# MCU.net
KiCad netlist of a schematic drawn in Altium Designer
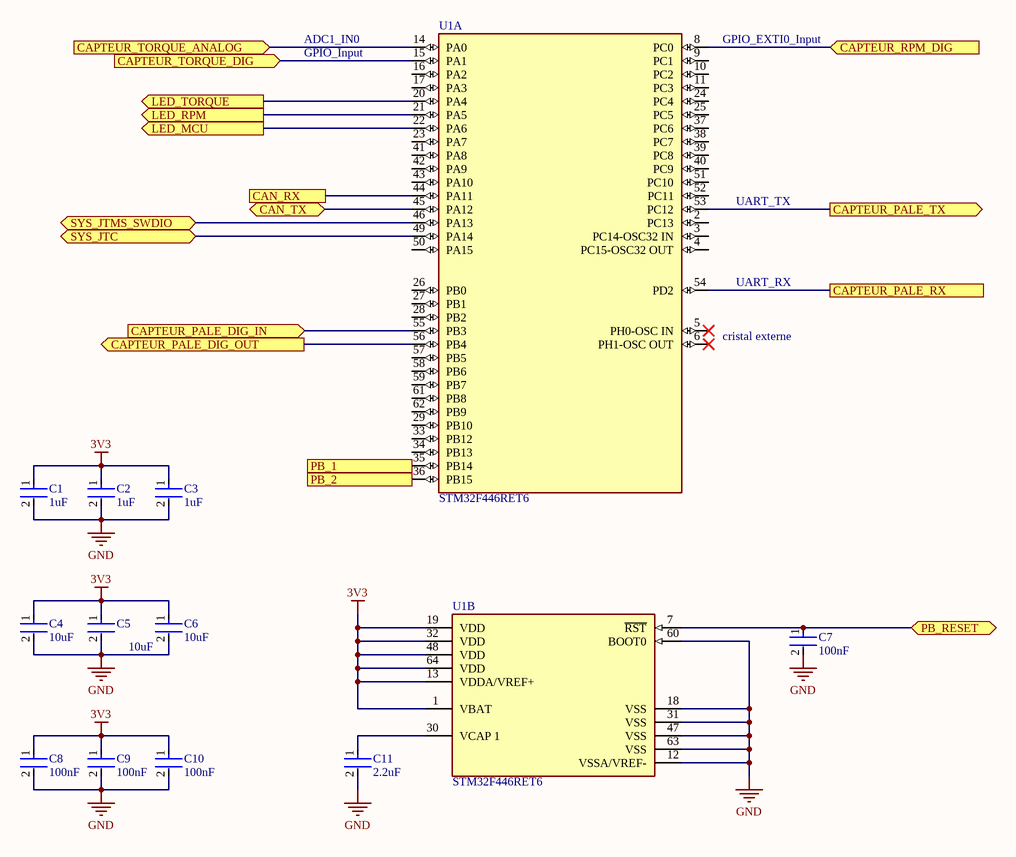
[diagram p0: MCU.SchDoc]

(export (version "E")
  (design (tool "Eeschema 10.0.6"))
  (components
    (comp (ref "C1")
      (value "1uF")
      (footprint "FP-GRM155-0_05-IPC_A")
      (description "Multilayer Ceramic Capacitor, 1 uF, 25 V, ± 20%, X5R, 0402 [1005 Metric]")
      (fields
        (field (name "MANUFACTURER") "Murata")
        (field (name "MANUFACTURER PART NUMBER") "GRM155R61E105MA12D")
      )
      (libsource (lib "chinook_lib_symbol_rotor") (part "GRM155R61E105MA12D"))
    )
    (comp (ref "C2")
      (value "1uF")
      (footprint "FP-GRM155-0_05-IPC_A")
      (description "Multilayer Ceramic Capacitor, 1 uF, 25 V, ± 20%, X5R, 0402 [1005 Metric]")
      (fields
        (field (name "MANUFACTURER") "Murata")
        (field (name "MANUFACTURER PART NUMBER") "GRM155R61E105MA12D")
      )
      (libsource (lib "chinook_lib_symbol_rotor") (part "GRM155R61E105MA12D"))
    )
    (comp (ref "C3")
      (value "1uF")
      (footprint "FP-GRM155-0_05-IPC_A")
      (description "Multilayer Ceramic Capacitor, 1 uF, 25 V, ± 20%, X5R, 0402 [1005 Metric]")
      (fields
        (field (name "MANUFACTURER") "Murata")
        (field (name "MANUFACTURER PART NUMBER") "GRM155R61E105MA12D")
      )
      (libsource (lib "chinook_lib_symbol_rotor") (part "GRM155R61E105MA12D"))
    )
    (comp (ref "C4")
      (value "10uF")
      (footprint "FP-GRM155-0_15-MFG")
      (description "Multilayer Ceramic Capacitor, 10 uF, 6.3 V, ± 20%, X5R, 0402 [1005 Metric]")
      (fields
        (field (name "MANUFACTURER") "Murata")
        (field (name "MANUFACTURER PART NUMBER") "GRM155R60J106ME15D")
      )
      (libsource (lib "chinook_lib_symbol_rotor") (part "GRM155R60J106ME15D"))
    )
    (comp (ref "C5")
      (value "10uF")
      (footprint "FP-GRM155-0_15-MFG")
      (description "Multilayer Ceramic Capacitor, 10 uF, 6.3 V, ± 20%, X5R, 0402 [1005 Metric]")
      (fields
        (field (name "MANUFACTURER") "Murata")
        (field (name "MANUFACTURER PART NUMBER") "GRM155R60J106ME15D")
      )
      (libsource (lib "chinook_lib_symbol_rotor") (part "GRM155R60J106ME15D"))
    )
    (comp (ref "C6")
      (value "10uF")
      (footprint "FP-GRM155-0_15-MFG")
      (description "Multilayer Ceramic Capacitor, 10 uF, 6.3 V, ± 20%, X5R, 0402 [1005 Metric]")
      (fields
        (field (name "MANUFACTURER") "Murata")
        (field (name "MANUFACTURER PART NUMBER") "GRM155R60J106ME15D")
      )
      (libsource (lib "chinook_lib_symbol_rotor") (part "GRM155R60J106ME15D"))
    )
    (comp (ref "C7")
      (value "100nF")
      (footprint "FP-CL278-IPC_A")
      (description "Multilayer Ceramic Capacitor, 0.1 uF, 25 V, ± 10%, X5R, 0402 [1005 Metric]")
      (fields
        (field (name "MANUFACTURER") "Samsung")
        (field (name "MANUFACTURER PART NUMBER") "CL05A104KA5NNNC")
      )
      (libsource (lib "chinook_lib_symbol_rotor") (part "CL05A104KA5NNNC"))
    )
    (comp (ref "C8")
      (value "100nF")
      (footprint "FP-CL278-IPC_A")
      (description "Multilayer Ceramic Capacitor, 0.1 uF, 25 V, ± 10%, X5R, 0402 [1005 Metric]")
      (fields
        (field (name "MANUFACTURER") "Samsung")
        (field (name "MANUFACTURER PART NUMBER") "CL05A104KA5NNNC")
      )
      (libsource (lib "chinook_lib_symbol_rotor") (part "CL05A104KA5NNNC"))
    )
    (comp (ref "C9")
      (value "100nF")
      (footprint "FP-CL278-IPC_A")
      (description "Multilayer Ceramic Capacitor, 0.1 uF, 25 V, ± 10%, X5R, 0402 [1005 Metric]")
      (fields
        (field (name "MANUFACTURER") "Samsung")
        (field (name "MANUFACTURER PART NUMBER") "CL05A104KA5NNNC")
      )
      (libsource (lib "chinook_lib_symbol_rotor") (part "CL05A104KA5NNNC"))
    )
    (comp (ref "C10")
      (value "100nF")
      (footprint "FP-CL278-IPC_A")
      (description "Multilayer Ceramic Capacitor, 0.1 uF, 25 V, ± 10%, X5R, 0402 [1005 Metric]")
      (fields
        (field (name "MANUFACTURER") "Samsung")
        (field (name "MANUFACTURER PART NUMBER") "CL05A104KA5NNNC")
      )
      (libsource (lib "chinook_lib_symbol_rotor") (part "CL05A104KA5NNNC"))
    )
    (comp (ref "C11")
      (value "2.2uF")
      (footprint "FP-GRM155-0_05-MFG")
      (description "Cap Ceramic 2.2uF 6.3V X6S 10% Pad SMD 0402 105°C T/R")
      (fields
        (field (name "MANUFACTURER") "Murata")
        (field (name "MANUFACTURER PART NUMBER") "GRM155C80J225KE95D")
      )
      (libsource (lib "chinook_lib_symbol_rotor") (part "GRM155C80J225KE95D"))
    )
    (comp (ref "U1")
      (value "STM32F446RET6")
      (footprint "FP-LQFP64-5W-IPC_A")
      (description "MCU 32-bit ARM Cortex M4 RISC 512KB Flash 2.5V/3.3V Medical 64-Pin LQFP Frame")
      (fields (field (name "MANUFACTURER") "STMicroelectronics"))
      (libsource (lib "chinook_lib_symbol_rotor") (part "STM32F446RET6"))
    )
  )
  (nets
    (net (code "1") (name "/CAN_RX") (class "Default")
      (node (ref "U1") (pin "44") (pinfunction "PA11_44") (pintype "bidirectional"))
    )
    (net (code "2") (name "/CAN_TX") (class "Default")
      (node (ref "U1") (pin "45") (pinfunction "PA12_45") (pintype "bidirectional"))
    )
    (net (code "3") (name "/CAPTEUR_PALE_DIG_IN") (class "Default")
      (node (ref "U1") (pin "55") (pinfunction "PB3_55") (pintype "bidirectional"))
    )
    (net (code "4") (name "/CAPTEUR_PALE_DIG_OUT") (class "Default")
      (node (ref "U1") (pin "56") (pinfunction "PB4_56") (pintype "bidirectional"))
    )
    (net (code "5") (name "/CAPTEUR_PALE_RX") (class "Default")
      (node (ref "U1") (pin "54") (pinfunction "PD2_54") (pintype "bidirectional"))
    )
    (net (code "6") (name "/CAPTEUR_PALE_TX") (class "Default")
      (node (ref "U1") (pin "53") (pinfunction "PC12_53") (pintype "bidirectional"))
    )
    (net (code "7") (name "/CAPTEUR_RPM_DIG") (class "Default")
      (node (ref "U1") (pin "8") (pinfunction "PC0_8") (pintype "bidirectional"))
    )
    (net (code "8") (name "/CAPTEUR_TORQUE_ANALOG") (class "Default")
      (node (ref "U1") (pin "14") (pinfunction "PA0_14") (pintype "bidirectional"))
    )
    (net (code "9") (name "/CAPTEUR_TORQUE_DIG") (class "Default")
      (node (ref "U1") (pin "15") (pinfunction "PA1_15") (pintype "bidirectional"))
    )
    (net (code "10") (name "/LED_MCU") (class "Default")
      (node (ref "U1") (pin "22") (pinfunction "PA6_22") (pintype "bidirectional"))
    )
    (net (code "11") (name "/LED_RPM") (class "Default")
      (node (ref "U1") (pin "21") (pinfunction "PA5_21") (pintype "bidirectional"))
    )
    (net (code "12") (name "/LED_TORQUE") (class "Default")
      (node (ref "U1") (pin "20") (pinfunction "PA4_20") (pintype "bidirectional"))
    )
    (net (code "13") (name "/PB_1") (class "Default")
      (node (ref "U1") (pin "35") (pinfunction "PB14_35") (pintype "bidirectional"))
    )
    (net (code "14") (name "/PB_2") (class "Default")
      (node (ref "U1") (pin "36") (pinfunction "PB15_36") (pintype "bidirectional"))
    )
    (net (code "15") (name "/PB_RESET") (class "Default")
      (node (ref "C7") (pin "1") (pinfunction "1_1") (pintype "passive"))
      (node (ref "U1") (pin "7") (pinfunction "~{RST}_7") (pintype "input"))
    )
    (net (code "16") (name "/SYS_JTC") (class "Default")
      (node (ref "U1") (pin "49") (pinfunction "PA14_49") (pintype "bidirectional"))
    )
    (net (code "17") (name "/SYS_JTMS_SWDIO") (class "Default")
      (node (ref "U1") (pin "46") (pinfunction "PA13_46") (pintype "bidirectional"))
    )
    (net (code "18") (name "3V3") (class "Default")
      (node (ref "C1") (pin "1") (pinfunction "1_1") (pintype "passive"))
      (node (ref "C10") (pin "1") (pinfunction "1_1") (pintype "passive"))
      (node (ref "C2") (pin "1") (pinfunction "1_1") (pintype "passive"))
      (node (ref "C3") (pin "1") (pinfunction "1_1") (pintype "passive"))
      (node (ref "C4") (pin "1") (pinfunction "1_1") (pintype "passive"))
      (node (ref "C5") (pin "1") (pinfunction "1_1") (pintype "passive"))
      (node (ref "C6") (pin "1") (pinfunction "1_1") (pintype "passive"))
      (node (ref "C8") (pin "1") (pinfunction "1_1") (pintype "passive"))
      (node (ref "C9") (pin "1") (pinfunction "1_1") (pintype "passive"))
      (node (ref "U1") (pin "1") (pinfunction "VBAT_1") (pintype "power_in"))
      (node (ref "U1") (pin "13") (pinfunction "VDDA/VREF+_13") (pintype "power_in"))
      (node (ref "U1") (pin "19") (pinfunction "VDD_19") (pintype "power_in"))
      (node (ref "U1") (pin "32") (pinfunction "VDD_32") (pintype "power_in"))
      (node (ref "U1") (pin "48") (pinfunction "VDD_48") (pintype "power_in"))
      (node (ref "U1") (pin "64") (pinfunction "VDD_64") (pintype "power_in"))
    )
    (net (code "19") (name "GND") (class "Default")
      (node (ref "C1") (pin "2") (pinfunction "2_2") (pintype "passive"))
      (node (ref "C10") (pin "2") (pinfunction "2_2") (pintype "passive"))
      (node (ref "C11") (pin "2") (pinfunction "2_2") (pintype "passive"))
      (node (ref "C2") (pin "2") (pinfunction "2_2") (pintype "passive"))
      (node (ref "C3") (pin "2") (pinfunction "2_2") (pintype "passive"))
      (node (ref "C4") (pin "2") (pinfunction "2_2") (pintype "passive"))
      (node (ref "C5") (pin "2") (pinfunction "2_2") (pintype "passive"))
      (node (ref "C6") (pin "2") (pinfunction "2_2") (pintype "passive"))
      (node (ref "C7") (pin "2") (pinfunction "2_2") (pintype "passive"))
      (node (ref "C8") (pin "2") (pinfunction "2_2") (pintype "passive"))
      (node (ref "C9") (pin "2") (pinfunction "2_2") (pintype "passive"))
      (node (ref "U1") (pin "12") (pinfunction "VSSA/VREF-_12") (pintype "power_in"))
      (node (ref "U1") (pin "18") (pinfunction "VSS_18") (pintype "power_in"))
      (node (ref "U1") (pin "31") (pinfunction "VSS_31") (pintype "power_in"))
      (node (ref "U1") (pin "47") (pinfunction "VSS_47") (pintype "power_in"))
      (node (ref "U1") (pin "60") (pinfunction "BOOT0_60") (pintype "input"))
      (node (ref "U1") (pin "63") (pinfunction "VSS_63") (pintype "power_in"))
    )
    (net (code "20") (name "Net-(U1B-VCAP_1)") (class "Default")
      (node (ref "C11") (pin "1") (pinfunction "1_1") (pintype "passive"))
      (node (ref "U1") (pin "30") (pinfunction "VCAP_1_30") (pintype "power_in"))
    )
    (net (code "21") (name "unconnected-(U1A-PA2-Pad16)") (class "Default")
      (node (ref "U1") (pin "16") (pinfunction "PA2_16") (pintype "bidirectional"))
    )
    (net (code "22") (name "unconnected-(U1A-PA3-Pad17)") (class "Default")
      (node (ref "U1") (pin "17") (pinfunction "PA3_17") (pintype "bidirectional"))
    )
    (net (code "23") (name "unconnected-(U1A-PA7-Pad23)") (class "Default")
      (node (ref "U1") (pin "23") (pinfunction "PA7_23") (pintype "bidirectional"))
    )
    (net (code "24") (name "unconnected-(U1A-PA8-Pad41)") (class "Default")
      (node (ref "U1") (pin "41") (pinfunction "PA8_41") (pintype "bidirectional"))
    )
    (net (code "25") (name "unconnected-(U1A-PA9-Pad42)") (class "Default")
      (node (ref "U1") (pin "42") (pinfunction "PA9_42") (pintype "bidirectional"))
    )
    (net (code "26") (name "unconnected-(U1A-PA10-Pad43)") (class "Default")
      (node (ref "U1") (pin "43") (pinfunction "PA10_43") (pintype "bidirectional"))
    )
    (net (code "27") (name "unconnected-(U1A-PA15-Pad50)") (class "Default")
      (node (ref "U1") (pin "50") (pinfunction "PA15_50") (pintype "bidirectional"))
    )
    (net (code "28") (name "unconnected-(U1A-PB0-Pad26)") (class "Default")
      (node (ref "U1") (pin "26") (pinfunction "PB0_26") (pintype "bidirectional"))
    )
    (net (code "29") (name "unconnected-(U1A-PB1-Pad27)") (class "Default")
      (node (ref "U1") (pin "27") (pinfunction "PB1_27") (pintype "bidirectional"))
    )
    (net (code "30") (name "unconnected-(U1A-PB2-Pad28)") (class "Default")
      (node (ref "U1") (pin "28") (pinfunction "PB2_28") (pintype "bidirectional"))
    )
    (net (code "31") (name "unconnected-(U1A-PB5-Pad57)") (class "Default")
      (node (ref "U1") (pin "57") (pinfunction "PB5_57") (pintype "bidirectional"))
    )
    (net (code "32") (name "unconnected-(U1A-PB6-Pad58)") (class "Default")
      (node (ref "U1") (pin "58") (pinfunction "PB6_58") (pintype "bidirectional"))
    )
    (net (code "33") (name "unconnected-(U1A-PB7-Pad59)") (class "Default")
      (node (ref "U1") (pin "59") (pinfunction "PB7_59") (pintype "bidirectional"))
    )
    (net (code "34") (name "unconnected-(U1A-PB8-Pad61)") (class "Default")
      (node (ref "U1") (pin "61") (pinfunction "PB8_61") (pintype "bidirectional"))
    )
    (net (code "35") (name "unconnected-(U1A-PB9-Pad62)") (class "Default")
      (node (ref "U1") (pin "62") (pinfunction "PB9_62") (pintype "bidirectional"))
    )
    (net (code "36") (name "unconnected-(U1A-PB10-Pad29)") (class "Default")
      (node (ref "U1") (pin "29") (pinfunction "PB10_29") (pintype "bidirectional"))
    )
    (net (code "37") (name "unconnected-(U1A-PB12-Pad33)") (class "Default")
      (node (ref "U1") (pin "33") (pinfunction "PB12_33") (pintype "bidirectional"))
    )
    (net (code "38") (name "unconnected-(U1A-PB13-Pad34)") (class "Default")
      (node (ref "U1") (pin "34") (pinfunction "PB13_34") (pintype "bidirectional"))
    )
    (net (code "39") (name "unconnected-(U1A-PC1-Pad9)") (class "Default")
      (node (ref "U1") (pin "9") (pinfunction "PC1_9") (pintype "bidirectional"))
    )
    (net (code "40") (name "unconnected-(U1A-PC2-Pad10)") (class "Default")
      (node (ref "U1") (pin "10") (pinfunction "PC2_10") (pintype "bidirectional"))
    )
    (net (code "41") (name "unconnected-(U1A-PC3-Pad11)") (class "Default")
      (node (ref "U1") (pin "11") (pinfunction "PC3_11") (pintype "bidirectional"))
    )
    (net (code "42") (name "unconnected-(U1A-PC4-Pad24)") (class "Default")
      (node (ref "U1") (pin "24") (pinfunction "PC4_24") (pintype "bidirectional"))
    )
    (net (code "43") (name "unconnected-(U1A-PC5-Pad25)") (class "Default")
      (node (ref "U1") (pin "25") (pinfunction "PC5_25") (pintype "bidirectional"))
    )
    (net (code "44") (name "unconnected-(U1A-PC6-Pad37)") (class "Default")
      (node (ref "U1") (pin "37") (pinfunction "PC6_37") (pintype "bidirectional"))
    )
    (net (code "45") (name "unconnected-(U1A-PC7-Pad38)") (class "Default")
      (node (ref "U1") (pin "38") (pinfunction "PC7_38") (pintype "bidirectional"))
    )
    (net (code "46") (name "unconnected-(U1A-PC8-Pad39)") (class "Default")
      (node (ref "U1") (pin "39") (pinfunction "PC8_39") (pintype "bidirectional"))
    )
    (net (code "47") (name "unconnected-(U1A-PC9-Pad40)") (class "Default")
      (node (ref "U1") (pin "40") (pinfunction "PC9_40") (pintype "bidirectional"))
    )
    (net (code "48") (name "unconnected-(U1A-PC10-Pad51)") (class "Default")
      (node (ref "U1") (pin "51") (pinfunction "PC10_51") (pintype "bidirectional"))
    )
    (net (code "49") (name "unconnected-(U1A-PC11-Pad52)") (class "Default")
      (node (ref "U1") (pin "52") (pinfunction "PC11_52") (pintype "bidirectional"))
    )
    (net (code "50") (name "unconnected-(U1A-PC13-Pad2)") (class "Default")
      (node (ref "U1") (pin "2") (pinfunction "PC13_2") (pintype "bidirectional"))
    )
    (net (code "51") (name "unconnected-(U1A-PC14-OSC32_IN-Pad3)") (class "Default")
      (node (ref "U1") (pin "3") (pinfunction "PC14-OSC32_IN_3") (pintype "bidirectional"))
    )
    (net (code "52") (name "unconnected-(U1A-PC15-OSC32_OUT-Pad4)") (class "Default")
      (node (ref "U1") (pin "4") (pinfunction "PC15-OSC32_OUT_4") (pintype "bidirectional"))
    )
    (net (code "53") (name "unconnected-(U1A-PH0-OSC_IN-Pad5)") (class "Default")
      (node (ref "U1") (pin "5") (pinfunction "PH0-OSC_IN_5") (pintype "bidirectional+no_connect"))
    )
    (net (code "54") (name "unconnected-(U1A-PH1-OSC_OUT-Pad6)") (class "Default")
      (node (ref "U1") (pin "6") (pinfunction "PH1-OSC_OUT_6") (pintype "bidirectional+no_connect"))
    )
  )
)
